# MOC3063S.net
KiCad netlist of a schematic drawn in Altium Designer
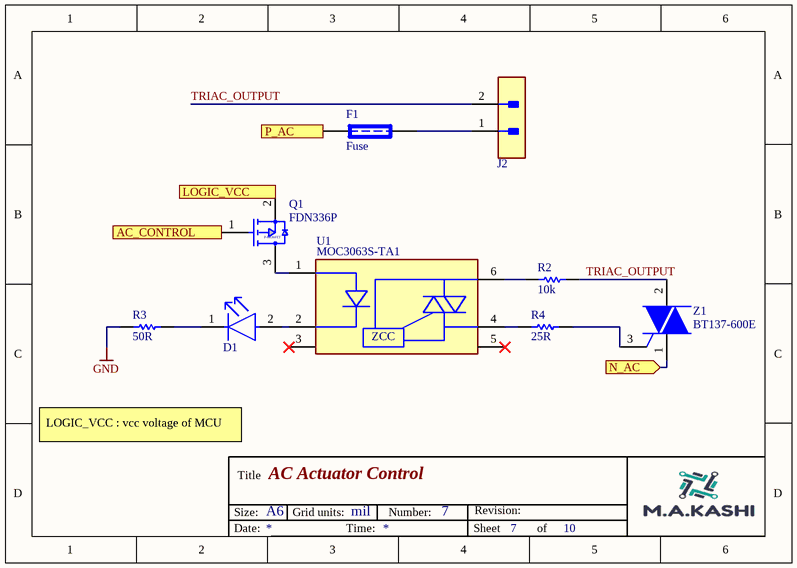
[diagram p0: MOC3063S.SchDoc]

(export (version "E")
  (design (tool "Eeschema 10.0.6"))
  (components
    (comp (ref "D1")
      (value "LED")
      (footprint "LED_1206_red_Dialight")
      (fields (field (name "PART NUMBER") "Add part number!"))
      (libsource (lib "E-component") (part "LED"))
    )
    (comp (ref "F1")
      (value "Fuse")
      (footprint "FUSE")
      (fields (field (name "PUBLISHER") "Altium Limited"))
      (libsource (lib "E-component") (part "Fuse"))
    )
    (comp (ref "J2")
      (value "Connector")
      (footprint "Phoenix 2 0D")
      (fields (field (name "MANUFACTURER") "JST") (field (name "DIGIKEY PART NUMBER") "455-2247-ND"))
      (libsource (lib "E-component") (part "Connector 2 pin"))
    )
    (comp (ref "Q1")
      (value "FDN336P")
      (footprint "ON_Semiconductor_527AG_IPC_A")
      (fields (field (name "PART NUMBER") "DMP3099L-13"))
      (libsource (lib "E-component") (part "FDN336P"))
    )
    (comp (ref "R2")
      (value "10k")
      (footprint "RES_0805_A")
      (description "octopart or digikey description!")
      (fields (field (name "PART NUMBER") "ERA-2AEB103X"))
      (libsource (lib "E-component") (part "Resistor"))
    )
    (comp (ref "R3")
      (value "50R")
      (footprint "RES_0805_A")
      (description "octopart or digikey description!")
      (fields (field (name "PART NUMBER") "RC0402JR-07100RL"))
      (libsource (lib "E-component") (part "Resistor"))
    )
    (comp (ref "R4")
      (value "25R")
      (footprint "RES_0805_A")
      (description "octopart or digikey description!")
      (fields (field (name "PART NUMBER") "ERA-2AEB103X"))
      (libsource (lib "E-component") (part "Resistor"))
    )
    (comp (ref "U1")
      (value "IC_Lite-On_Inc._MOC3063S-TA1_eec")
      (footprint "Lite-On_Inc._SMD6_0")
      (description "IC OPTOISOLATOR 5KV TRIAC 6SMD")
      (fields
        (field (name "MANUFACTURER") "Lite-On Inc.")
        (field (name "MOUSER PART NUMBER") "859-MOC3063S-TA1")
        (field (name "PART NUMBER") "MOC3063S-TA1")
      )
      (libsource (lib "E-component") (part "IC_Lite-On_Inc._MOC3063S-TA1_eec"))
    )
    (comp (ref "Z1")
      (value "BT137-600E")
      (footprint "sot78")
      (fields (field (name "PART NUMBER") "Z0103MN"))
      (libsource (lib "E-component") (part "BT137-600E"))
    )
  )
  (nets
    (net (code "1") (name "/AC_CONTROL") (class "Default")
      (node (ref "Q1") (pin "1") (pinfunction "G_1") (pintype "passive"))
    )
    (net (code "2") (name "/LOGIC_VCC") (class "Default")
      (node (ref "Q1") (pin "2") (pinfunction "S_2") (pintype "passive"))
    )
    (net (code "3") (name "/N_AC") (class "Default")
      (node (ref "Z1") (pin "1") (pinfunction "T1_1") (pintype "passive"))
    )
    (net (code "4") (name "/P_AC") (class "Default")
      (node (ref "F1") (pin "1") (pinfunction "1_1") (pintype "passive"))
    )
    (net (code "5") (name "/TRIAC_OUTPUT") (class "Default")
      (node (ref "J2") (pin "2") (pinfunction "2_2") (pintype "passive"))
      (node (ref "R2") (pin "2") (pinfunction "2_2") (pintype "passive"))
      (node (ref "Z1") (pin "2") (pinfunction "T2_2") (pintype "passive"))
    )
    (net (code "6") (name "GND") (class "Default")
      (node (ref "R3") (pin "1") (pinfunction "1_1") (pintype "passive"))
    )
    (net (code "7") (name "Net-(D1-A)") (class "Default")
      (node (ref "D1") (pin "2") (pinfunction "A_2") (pintype "passive"))
      (node (ref "U1") (pin "2") (pinfunction "C_2") (pintype "passive"))
    )
    (net (code "8") (name "Net-(D1-C)") (class "Default")
      (node (ref "D1") (pin "1") (pinfunction "C_1") (pintype "passive"))
      (node (ref "R3") (pin "2") (pinfunction "2_2") (pintype "passive"))
    )
    (net (code "9") (name "Net-(F1-Pad2)") (class "Default")
      (node (ref "F1") (pin "2") (pinfunction "2_2") (pintype "passive"))
      (node (ref "J2") (pin "1") (pinfunction "1_1") (pintype "passive"))
    )
    (net (code "10") (name "Net-(Q1-D)") (class "Default")
      (node (ref "Q1") (pin "3") (pinfunction "D_3") (pintype "passive"))
      (node (ref "U1") (pin "1") (pinfunction "A_1") (pintype "passive"))
    )
    (net (code "11") (name "Net-(U1-1_MAIN_TERMINAL)") (class "Default")
      (node (ref "R4") (pin "1") (pinfunction "1_1") (pintype "passive"))
      (node (ref "U1") (pin "4") (pinfunction "1_MAIN_TERMINAL_4") (pintype "passive"))
    )
    (net (code "12") (name "Net-(U1-2_MAIN_TERMINAL)") (class "Default")
      (node (ref "R2") (pin "1") (pinfunction "1_1") (pintype "passive"))
      (node (ref "U1") (pin "6") (pinfunction "2_MAIN_TERMINAL_6") (pintype "passive"))
    )
    (net (code "13") (name "Net-(Z1-G)") (class "Default")
      (node (ref "R4") (pin "2") (pinfunction "2_2") (pintype "passive"))
      (node (ref "Z1") (pin "3") (pinfunction "G_3") (pintype "passive"))
    )
    (net (code "14") (name "unconnected-(U1-NC-Pad3)") (class "Default")
      (node (ref "U1") (pin "3") (pinfunction "NC_3") (pintype "passive+no_connect"))
    )
    (net (code "15") (name "unconnected-(U1-SUBSTRATE-Pad5)") (class "Default")
      (node (ref "U1") (pin "5") (pinfunction "SUBSTRATE_5") (pintype "passive+no_connect"))
    )
  )
)
